# Sensors.net
KiCad netlist of a schematic drawn in Altium Designer
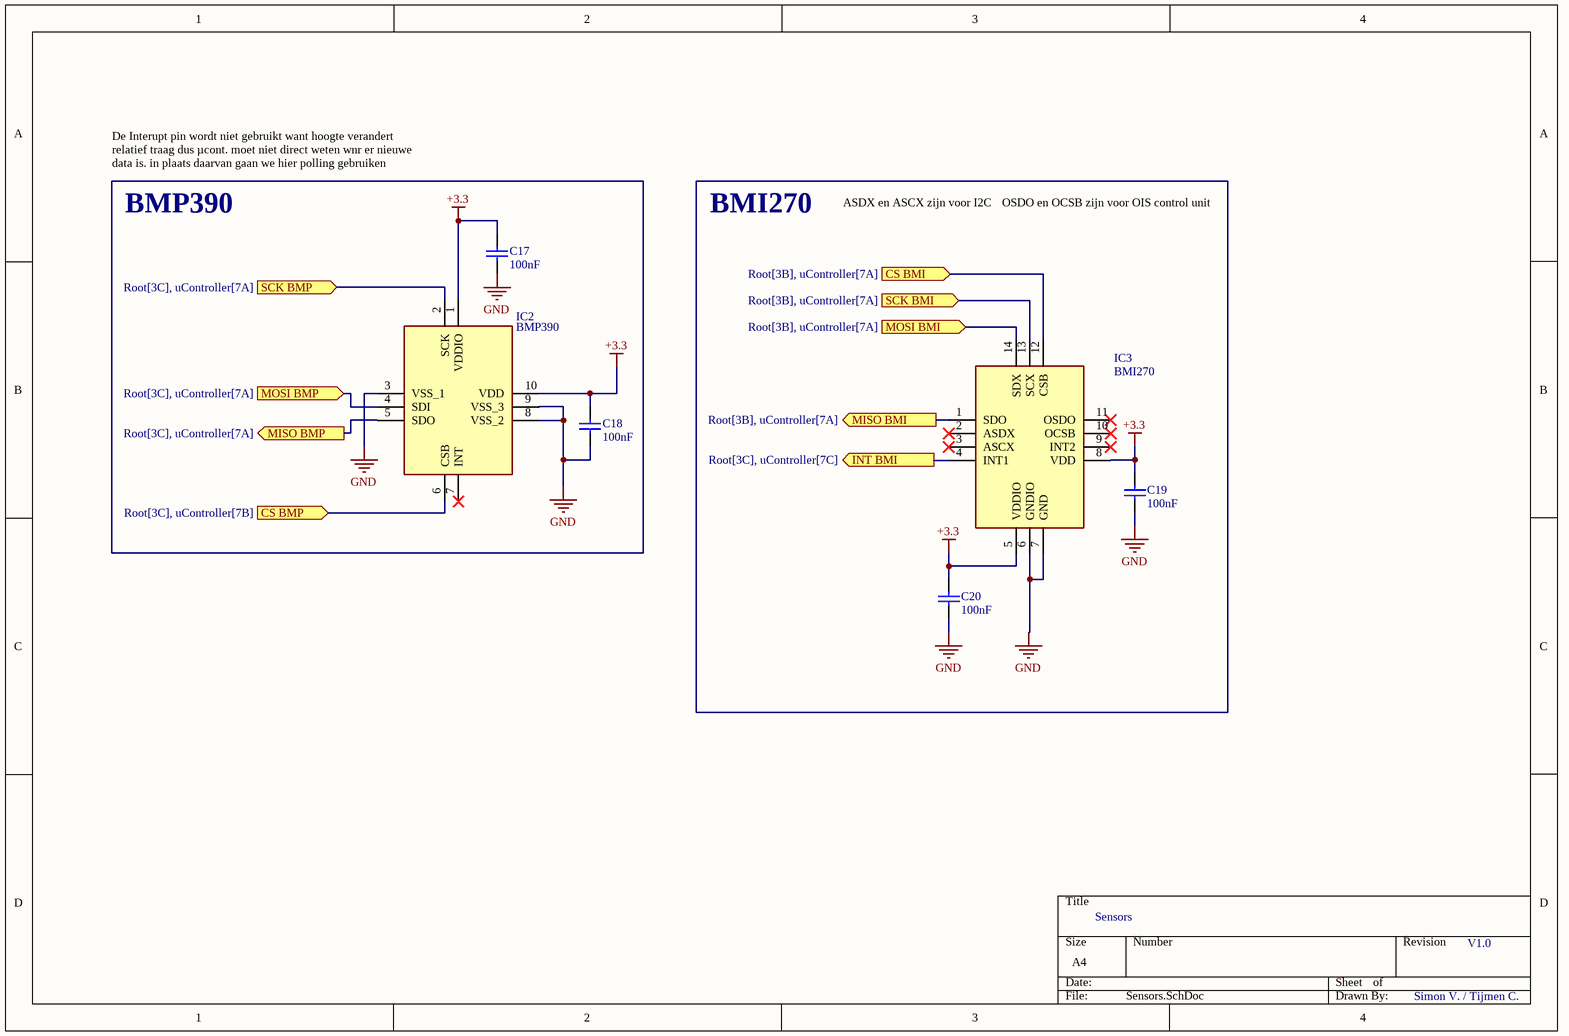
[diagram p0: Sensors.SchDoc]

(export (version "E")
  (design (tool "Eeschema 10.0.6"))
  (components
    (comp (ref "C17")
      (value "100nF")
      (footprint "CAPC1608X92X38ML15T08")
      (fields (field (name "PART NUMBER") "VJ0603Y104MXXAC") (field (name "MANUFACTURER") "Vitramon"))
      (libsource (lib "Altium Content Vault") (part "CAP"))
    )
    (comp (ref "C18")
      (value "100nF")
      (footprint "CAPC1608X92X38ML15T08")
      (fields (field (name "PART NUMBER") "VJ0603Y104MXXAC") (field (name "MANUFACTURER") "Vitramon"))
      (libsource (lib "Altium Content Vault") (part "CAP"))
    )
    (comp (ref "C19")
      (value "100nF")
      (footprint "CAPC1608X92X38ML15T08")
      (fields (field (name "PART NUMBER") "VJ0603Y104MXXAC") (field (name "MANUFACTURER") "Vitramon"))
      (libsource (lib "Altium Content Vault") (part "CAP"))
    )
    (comp (ref "C20")
      (value "100nF")
      (footprint "CAPC1608X92X38ML15T08")
      (fields (field (name "PART NUMBER") "VJ0603Y104MXXAC") (field (name "MANUFACTURER") "Vitramon"))
      (libsource (lib "Altium Content Vault") (part "CAP"))
    )
    (comp (ref "IC2")
      (value "BMP390")
      (footprint "SamacSys:BMP390")
      (description "Integrated Circuit")
      (fields (field (name "MOUSER PART NUMBER") "262-BMP390"))
      (libsource (lib "*") (part "BMP390"))
    )
    (comp (ref "IC3")
      (value "BMI270")
      (footprint "SamacSys:BMI270")
      (description "Integrated Circuit")
      (fields (field (name "MOUSER PART NUMBER") "262-BMI270"))
      (libsource (lib "*") (part "BMI270"))
    )
  )
  (nets
    (net (code "1") (name "+3.3") (class "Default")
      (node (ref "C17") (pin "2") (pinfunction "2_2") (pintype "passive"))
      (node (ref "C18") (pin "2") (pinfunction "2_2") (pintype "passive"))
      (node (ref "C19") (pin "2") (pinfunction "2_2") (pintype "passive"))
      (node (ref "C20") (pin "2") (pinfunction "2_2") (pintype "passive"))
      (node (ref "IC2") (pin "1") (pinfunction "VDDIO_1") (pintype "passive"))
      (node (ref "IC2") (pin "10") (pinfunction "VDD_10") (pintype "passive"))
      (node (ref "IC3") (pin "5") (pinfunction "VDDIO_5") (pintype "passive"))
      (node (ref "IC3") (pin "8") (pinfunction "VDD_8") (pintype "passive"))
    )
    (net (code "2") (name "/CS BMI") (class "Default")
      (node (ref "IC3") (pin "12") (pinfunction "CSB_12") (pintype "passive"))
    )
    (net (code "3") (name "/CS BMP") (class "Default")
      (node (ref "IC2") (pin "6") (pinfunction "CSB_6") (pintype "passive"))
    )
    (net (code "4") (name "/INT BMI") (class "Default")
      (node (ref "IC3") (pin "4") (pinfunction "INT1_4") (pintype "passive"))
    )
    (net (code "5") (name "/MISO BMI") (class "Default")
      (node (ref "IC3") (pin "1") (pinfunction "SDO_1") (pintype "passive"))
    )
    (net (code "6") (name "/MISO BMP") (class "Default")
      (node (ref "IC2") (pin "5") (pinfunction "SDO_5") (pintype "passive"))
    )
    (net (code "7") (name "/MOSI BMI") (class "Default")
      (node (ref "IC3") (pin "14") (pinfunction "SDX_14") (pintype "passive"))
    )
    (net (code "8") (name "/MOSI BMP") (class "Default")
      (node (ref "IC2") (pin "4") (pinfunction "SDI_4") (pintype "passive"))
    )
    (net (code "9") (name "/SCK BMI") (class "Default")
      (node (ref "IC3") (pin "13") (pinfunction "SCX_13") (pintype "passive"))
    )
    (net (code "10") (name "/SCK BMP") (class "Default")
      (node (ref "IC2") (pin "2") (pinfunction "SCK_2") (pintype "passive"))
    )
    (net (code "11") (name "GND") (class "Default")
      (node (ref "C17") (pin "1") (pinfunction "1_1") (pintype "passive"))
      (node (ref "C18") (pin "1") (pinfunction "1_1") (pintype "passive"))
      (node (ref "C19") (pin "1") (pinfunction "1_1") (pintype "passive"))
      (node (ref "C20") (pin "1") (pinfunction "1_1") (pintype "passive"))
      (node (ref "IC2") (pin "3") (pinfunction "VSS_1_3") (pintype "passive"))
      (node (ref "IC2") (pin "8") (pinfunction "VSS_2_8") (pintype "passive"))
      (node (ref "IC2") (pin "9") (pinfunction "VSS_3_9") (pintype "passive"))
      (node (ref "IC3") (pin "6") (pinfunction "GNDIO_6") (pintype "passive"))
      (node (ref "IC3") (pin "7") (pinfunction "GND_7") (pintype "passive"))
    )
    (net (code "12") (name "unconnected-(IC2-INT-Pad7)") (class "Default")
      (node (ref "IC2") (pin "7") (pinfunction "INT_7") (pintype "passive+no_connect"))
    )
    (net (code "13") (name "unconnected-(IC3-ASCX-Pad3)") (class "Default")
      (node (ref "IC3") (pin "3") (pinfunction "ASCX_3") (pintype "passive+no_connect"))
    )
    (net (code "14") (name "unconnected-(IC3-ASDX-Pad2)") (class "Default")
      (node (ref "IC3") (pin "2") (pinfunction "ASDX_2") (pintype "passive+no_connect"))
    )
    (net (code "15") (name "unconnected-(IC3-INT2-Pad9)") (class "Default")
      (node (ref "IC3") (pin "9") (pinfunction "INT2_9") (pintype "passive+no_connect"))
    )
    (net (code "16") (name "unconnected-(IC3-OCSB-Pad10)") (class "Default")
      (node (ref "IC3") (pin "10") (pinfunction "OCSB_10") (pintype "passive+no_connect"))
    )
    (net (code "17") (name "unconnected-(IC3-OSDO-Pad11)") (class "Default")
      (node (ref "IC3") (pin "11") (pinfunction "OSDO_11") (pintype "passive+no_connect"))
    )
  )
)
